# desk-controller.net
KiCad netlist of a schematic drawn in EAGLE
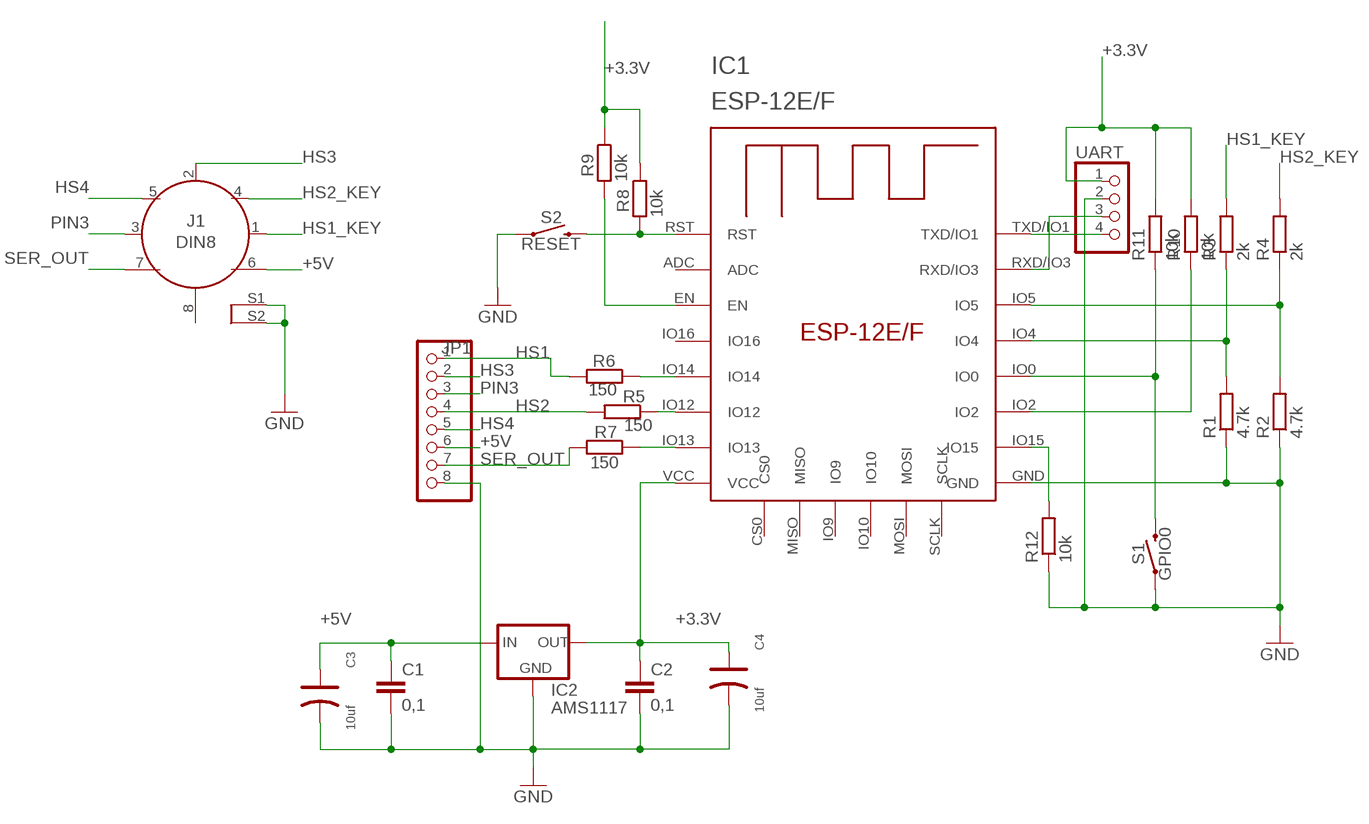
[diagram p0: schematic, sheet 1]

(export (version "E")
  (design (tool "Eeschema 10.0.6"))
  (components
    (comp (ref "C1")
      (value "0,1")
      (footprint "eagle-import:C1206")
      (libsource (lib "eagle-import") (part "C-EUC1206"))
    )
    (comp (ref "C2")
      (value "0,1")
      (footprint "eagle-import:C1206")
      (libsource (lib "eagle-import") (part "C-EUC1206"))
    )
    (comp (ref "C3")
      (value "10uf")
      (footprint "eagle-import:AVX-B")
      (fields (field (name "MPN") "TAJB106K016RNJ"))
      (libsource (lib "eagle-import") (part "TANTALUM-SMD-10UF-16V-10%(AVX-B)"))
    )
    (comp (ref "C4")
      (value "10uf")
      (footprint "eagle-import:AVX-B")
      (fields (field (name "MPN") "TAJB106K016RNJ"))
      (libsource (lib "eagle-import") (part "TANTALUM-SMD-10UF-16V-10%(AVX-B)"))
    )
    (comp (ref "IC1")
      (value "ESP-12E/F")
      (footprint "eagle-import:ESP-12E")
      (libsource (lib "eagle-import") (part "ESP-12E/F"))
    )
    (comp (ref "IC2")
      (value "AMS1117")
      (footprint "eagle-import:SOT223")
      (libsource (lib "eagle-import") (part "LM1117"))
    )
    (comp (ref "J1")
      (value "DIN8")
      (footprint "eagle-import:DIN8-RA-PTH")
      (libsource (lib "eagle-import") (part "DIN8"))
    )
    (comp (ref "JP1")
      (value "PINHD-1X8")
      (footprint "eagle-import:1X08")
      (libsource (lib "eagle-import") (part "PINHD-1X8"))
    )
    (comp (ref "R1")
      (value "4.7k")
      (footprint "eagle-import:R0805")
      (libsource (lib "eagle-import") (part "R-EU_R0805"))
    )
    (comp (ref "R2")
      (value "4.7k")
      (footprint "eagle-import:R0805")
      (libsource (lib "eagle-import") (part "R-EU_R0805"))
    )
    (comp (ref "R3")
      (value "2k")
      (footprint "eagle-import:R0805")
      (libsource (lib "eagle-import") (part "R-EU_R0805"))
    )
    (comp (ref "R4")
      (value "2k")
      (footprint "eagle-import:R0805")
      (libsource (lib "eagle-import") (part "R-EU_R0805"))
    )
    (comp (ref "R5")
      (value "150")
      (footprint "eagle-import:R0805")
      (libsource (lib "eagle-import") (part "R-EU_R0805"))
    )
    (comp (ref "R6")
      (value "150")
      (footprint "eagle-import:R0805")
      (libsource (lib "eagle-import") (part "R-EU_R0805"))
    )
    (comp (ref "R7")
      (value "150")
      (footprint "eagle-import:R0805")
      (libsource (lib "eagle-import") (part "R-EU_R0805"))
    )
    (comp (ref "R8")
      (value "10k")
      (footprint "eagle-import:R0805")
      (libsource (lib "eagle-import") (part "R-EU_R0805"))
    )
    (comp (ref "R9")
      (value "10k")
      (footprint "eagle-import:R0805")
      (libsource (lib "eagle-import") (part "R-EU_R0805"))
    )
    (comp (ref "R10")
      (value "10k")
      (footprint "eagle-import:R0805")
      (libsource (lib "eagle-import") (part "R-EU_R0805"))
    )
    (comp (ref "R11")
      (value "10k")
      (footprint "eagle-import:R0805")
      (libsource (lib "eagle-import") (part "R-EU_R0805"))
    )
    (comp (ref "R12")
      (value "10k")
      (footprint "eagle-import:R0805")
      (libsource (lib "eagle-import") (part "R-EU_R0805"))
    )
    (comp (ref "S1")
      (value "GPIO0")
      (footprint "eagle-import:TACTILE_SWITCH_PTH_RIGHT_ANGLE_KIT")
      (libsource (lib "eagle-import") (part "MOMENTARY-SWITCH-SPST-PTH-RIGHT-ANGLE-KIT"))
    )
    (comp (ref "S2")
      (value "RESET")
      (footprint "eagle-import:TACTILE_SWITCH_PTH_RIGHT_ANGLE_KIT")
      (libsource (lib "eagle-import") (part "MOMENTARY-SWITCH-SPST-PTH-RIGHT-ANGLE-KIT"))
    )
    (comp (ref "UART")
      (value "PINHD-1X4")
      (footprint "eagle-import:1X04")
      (libsource (lib "eagle-import") (part "PINHD-1X4"))
    )
  )
  (nets
    (net (code "1") (name "/+3.3V") (class "Default")
      (node (ref "C2") (pin "1") (pinfunction "1_1") (pintype "passive"))
      (node (ref "C4") (pin "+") (pinfunction "+_+") (pintype "passive"))
      (node (ref "IC1") (pin "VCC") (pinfunction "VCC_VCC") (pintype "power_in"))
      (node (ref "IC2") (pin "2") (pinfunction "OUT_2") (pintype "passive"))
      (node (ref "R10") (pin "2") (pinfunction "2_2") (pintype "passive"))
      (node (ref "R11") (pin "2") (pinfunction "2_2") (pintype "passive"))
      (node (ref "R8") (pin "1") (pinfunction "1_1") (pintype "passive"))
      (node (ref "R9") (pin "1") (pinfunction "1_1") (pintype "passive"))
      (node (ref "UART") (pin "1") (pinfunction "1_1") (pintype "passive"))
    )
    (net (code "2") (name "/+5V") (class "Default")
      (node (ref "C1") (pin "1") (pinfunction "1_1") (pintype "passive"))
      (node (ref "C3") (pin "+") (pinfunction "+_+") (pintype "passive"))
      (node (ref "IC2") (pin "3") (pinfunction "IN_3") (pintype "input"))
      (node (ref "J1") (pin "6") (pinfunction "6_6") (pintype "bidirectional"))
      (node (ref "JP1") (pin "6") (pinfunction "6_6") (pintype "passive"))
    )
    (net (code "3") (name "/HS1") (class "Default")
      (node (ref "JP1") (pin "1") (pinfunction "1_1") (pintype "passive"))
      (node (ref "R6") (pin "2") (pinfunction "2_2") (pintype "passive"))
    )
    (net (code "4") (name "/HS1_KEY") (class "Default")
      (node (ref "J1") (pin "1") (pinfunction "1_1") (pintype "bidirectional"))
      (node (ref "R3") (pin "2") (pinfunction "2_2") (pintype "passive"))
    )
    (net (code "5") (name "/HS2") (class "Default")
      (node (ref "JP1") (pin "4") (pinfunction "4_4") (pintype "passive"))
      (node (ref "R5") (pin "2") (pinfunction "2_2") (pintype "passive"))
    )
    (net (code "6") (name "/HS2_KEY") (class "Default")
      (node (ref "J1") (pin "4") (pinfunction "4_4") (pintype "bidirectional"))
      (node (ref "R4") (pin "2") (pinfunction "2_2") (pintype "passive"))
    )
    (net (code "7") (name "/HS3") (class "Default")
      (node (ref "J1") (pin "2") (pinfunction "2_2") (pintype "bidirectional"))
      (node (ref "JP1") (pin "2") (pinfunction "2_2") (pintype "passive"))
    )
    (net (code "8") (name "/HS4") (class "Default")
      (node (ref "J1") (pin "5") (pinfunction "5_5") (pintype "bidirectional"))
      (node (ref "JP1") (pin "5") (pinfunction "5_5") (pintype "passive"))
    )
    (net (code "9") (name "/PIN3") (class "Default")
      (node (ref "J1") (pin "3") (pinfunction "3_3") (pintype "bidirectional"))
      (node (ref "JP1") (pin "3") (pinfunction "3_3") (pintype "passive"))
    )
    (net (code "10") (name "/SER_OUT") (class "Default")
      (node (ref "J1") (pin "7") (pinfunction "7_7") (pintype "bidirectional"))
      (node (ref "JP1") (pin "7") (pinfunction "7_7") (pintype "passive"))
      (node (ref "R7") (pin "2") (pinfunction "2_2") (pintype "passive"))
    )
    (net (code "11") (name "GND") (class "Default")
      (node (ref "C1") (pin "2") (pinfunction "2_2") (pintype "passive"))
      (node (ref "C2") (pin "2") (pinfunction "2_2") (pintype "passive"))
      (node (ref "C3") (pin "-") (pinfunction "-_-") (pintype "passive"))
      (node (ref "C4") (pin "-") (pinfunction "-_-") (pintype "passive"))
      (node (ref "IC1") (pin "GND") (pinfunction "GND_GND") (pintype "power_in"))
      (node (ref "IC2") (pin "1") (pinfunction "GND_1") (pintype "input"))
      (node (ref "J1") (pin "S1") (pinfunction "SHIELD_S1") (pintype "bidirectional"))
      (node (ref "J1") (pin "S2") (pinfunction "SHIELD_S2") (pintype "bidirectional"))
      (node (ref "JP1") (pin "8") (pinfunction "8_8") (pintype "passive"))
      (node (ref "R1") (pin "1") (pinfunction "1_1") (pintype "passive"))
      (node (ref "R12") (pin "1") (pinfunction "1_1") (pintype "passive"))
      (node (ref "R2") (pin "1") (pinfunction "1_1") (pintype "passive"))
      (node (ref "S1") (pin "1") (pinfunction "1_1") (pintype "passive"))
      (node (ref "S2") (pin "1") (pinfunction "1_1") (pintype "passive"))
      (node (ref "UART") (pin "2") (pinfunction "2_2") (pintype "passive"))
    )
    (net (code "12") (name "Net-(IC1-PadEN)") (class "Default")
      (node (ref "IC1") (pin "EN") (pinfunction "EN_EN") (pintype "bidirectional"))
      (node (ref "R9") (pin "2") (pinfunction "2_2") (pintype "passive"))
    )
    (net (code "13") (name "Net-(IC1-PadIO0)") (class "Default")
      (node (ref "IC1") (pin "IO0") (pinfunction "IO0_IO0") (pintype "bidirectional"))
      (node (ref "R11") (pin "1") (pinfunction "1_1") (pintype "passive"))
      (node (ref "S1") (pin "2") (pinfunction "2_2") (pintype "passive"))
    )
    (net (code "14") (name "Net-(IC1-PadIO2)") (class "Default")
      (node (ref "IC1") (pin "IO2") (pinfunction "IO2_IO2") (pintype "bidirectional"))
      (node (ref "R10") (pin "1") (pinfunction "1_1") (pintype "passive"))
    )
    (net (code "15") (name "Net-(IC1-PadIO4)") (class "Default")
      (node (ref "IC1") (pin "IO4") (pinfunction "IO4_IO4") (pintype "bidirectional"))
      (node (ref "R1") (pin "2") (pinfunction "2_2") (pintype "passive"))
      (node (ref "R3") (pin "1") (pinfunction "1_1") (pintype "passive"))
    )
    (net (code "16") (name "Net-(IC1-PadIO5)") (class "Default")
      (node (ref "IC1") (pin "IO5") (pinfunction "IO5_IO5") (pintype "bidirectional"))
      (node (ref "R2") (pin "2") (pinfunction "2_2") (pintype "passive"))
      (node (ref "R4") (pin "1") (pinfunction "1_1") (pintype "passive"))
    )
    (net (code "17") (name "Net-(IC1-PadIO12)") (class "Default")
      (node (ref "IC1") (pin "IO12") (pinfunction "IO12_IO12") (pintype "bidirectional"))
      (node (ref "R5") (pin "1") (pinfunction "1_1") (pintype "passive"))
    )
    (net (code "18") (name "Net-(IC1-PadIO13)") (class "Default")
      (node (ref "IC1") (pin "IO13") (pinfunction "IO13_IO13") (pintype "bidirectional"))
      (node (ref "R7") (pin "1") (pinfunction "1_1") (pintype "passive"))
    )
    (net (code "19") (name "Net-(IC1-PadIO14)") (class "Default")
      (node (ref "IC1") (pin "IO14") (pinfunction "IO14_IO14") (pintype "bidirectional"))
      (node (ref "R6") (pin "1") (pinfunction "1_1") (pintype "passive"))
    )
    (net (code "20") (name "Net-(IC1-PadIO15)") (class "Default")
      (node (ref "IC1") (pin "IO15") (pinfunction "IO15_IO15") (pintype "bidirectional"))
      (node (ref "R12") (pin "2") (pinfunction "2_2") (pintype "passive"))
    )
    (net (code "21") (name "Net-(IC1-PadRST)") (class "Default")
      (node (ref "IC1") (pin "RST") (pinfunction "RST_RST") (pintype "input"))
      (node (ref "R8") (pin "2") (pinfunction "2_2") (pintype "passive"))
      (node (ref "S2") (pin "2") (pinfunction "2_2") (pintype "passive"))
    )
    (net (code "22") (name "Net-(IC1-PadRXD{slash}IO3)") (class "Default")
      (node (ref "IC1") (pin "RXD/IO3") (pinfunction "RXD/IO3_RXD/IO3") (pintype "bidirectional"))
      (node (ref "UART") (pin "3") (pinfunction "3_3") (pintype "passive"))
    )
    (net (code "23") (name "Net-(IC1-PadTXD{slash}IO1)") (class "Default")
      (node (ref "IC1") (pin "TXD/IO1") (pinfunction "TXD/IO1_TXD/IO1") (pintype "bidirectional"))
      (node (ref "UART") (pin "4") (pinfunction "4_4") (pintype "passive"))
    )
    (net (code "24") (name "unconnected-(IC1-PadADC)") (class "Default")
      (node (ref "IC1") (pin "ADC") (pinfunction "ADC_ADC") (pintype "bidirectional"))
    )
    (net (code "25") (name "unconnected-(IC1-PadCS0)") (class "Default")
      (node (ref "IC1") (pin "CS0") (pinfunction "CS0_CS0") (pintype "bidirectional"))
    )
    (net (code "26") (name "unconnected-(IC1-PadIO9)") (class "Default")
      (node (ref "IC1") (pin "IO9") (pinfunction "IO9_IO9") (pintype "bidirectional"))
    )
    (net (code "27") (name "unconnected-(IC1-PadIO10)") (class "Default")
      (node (ref "IC1") (pin "IO10") (pinfunction "IO10_IO10") (pintype "bidirectional"))
    )
    (net (code "28") (name "unconnected-(IC1-PadIO16)") (class "Default")
      (node (ref "IC1") (pin "IO16") (pinfunction "IO16_IO16") (pintype "bidirectional"))
    )
    (net (code "29") (name "unconnected-(IC1-PadMISO)") (class "Default")
      (node (ref "IC1") (pin "MISO") (pinfunction "MISO_MISO") (pintype "bidirectional"))
    )
    (net (code "30") (name "unconnected-(IC1-PadMOSI)") (class "Default")
      (node (ref "IC1") (pin "MOSI") (pinfunction "MOSI_MOSI") (pintype "bidirectional"))
    )
    (net (code "31") (name "unconnected-(IC1-PadSCLK)") (class "Default")
      (node (ref "IC1") (pin "SCLK") (pinfunction "SCLK_SCLK") (pintype "bidirectional"))
    )
    (net (code "32") (name "unconnected-(J1-Pad8)") (class "Default")
      (node (ref "J1") (pin "8") (pinfunction "8_8") (pintype "bidirectional"))
    )
  )
)
